# multiplexers.net
KiCad netlist of a schematic drawn in Altium Designer
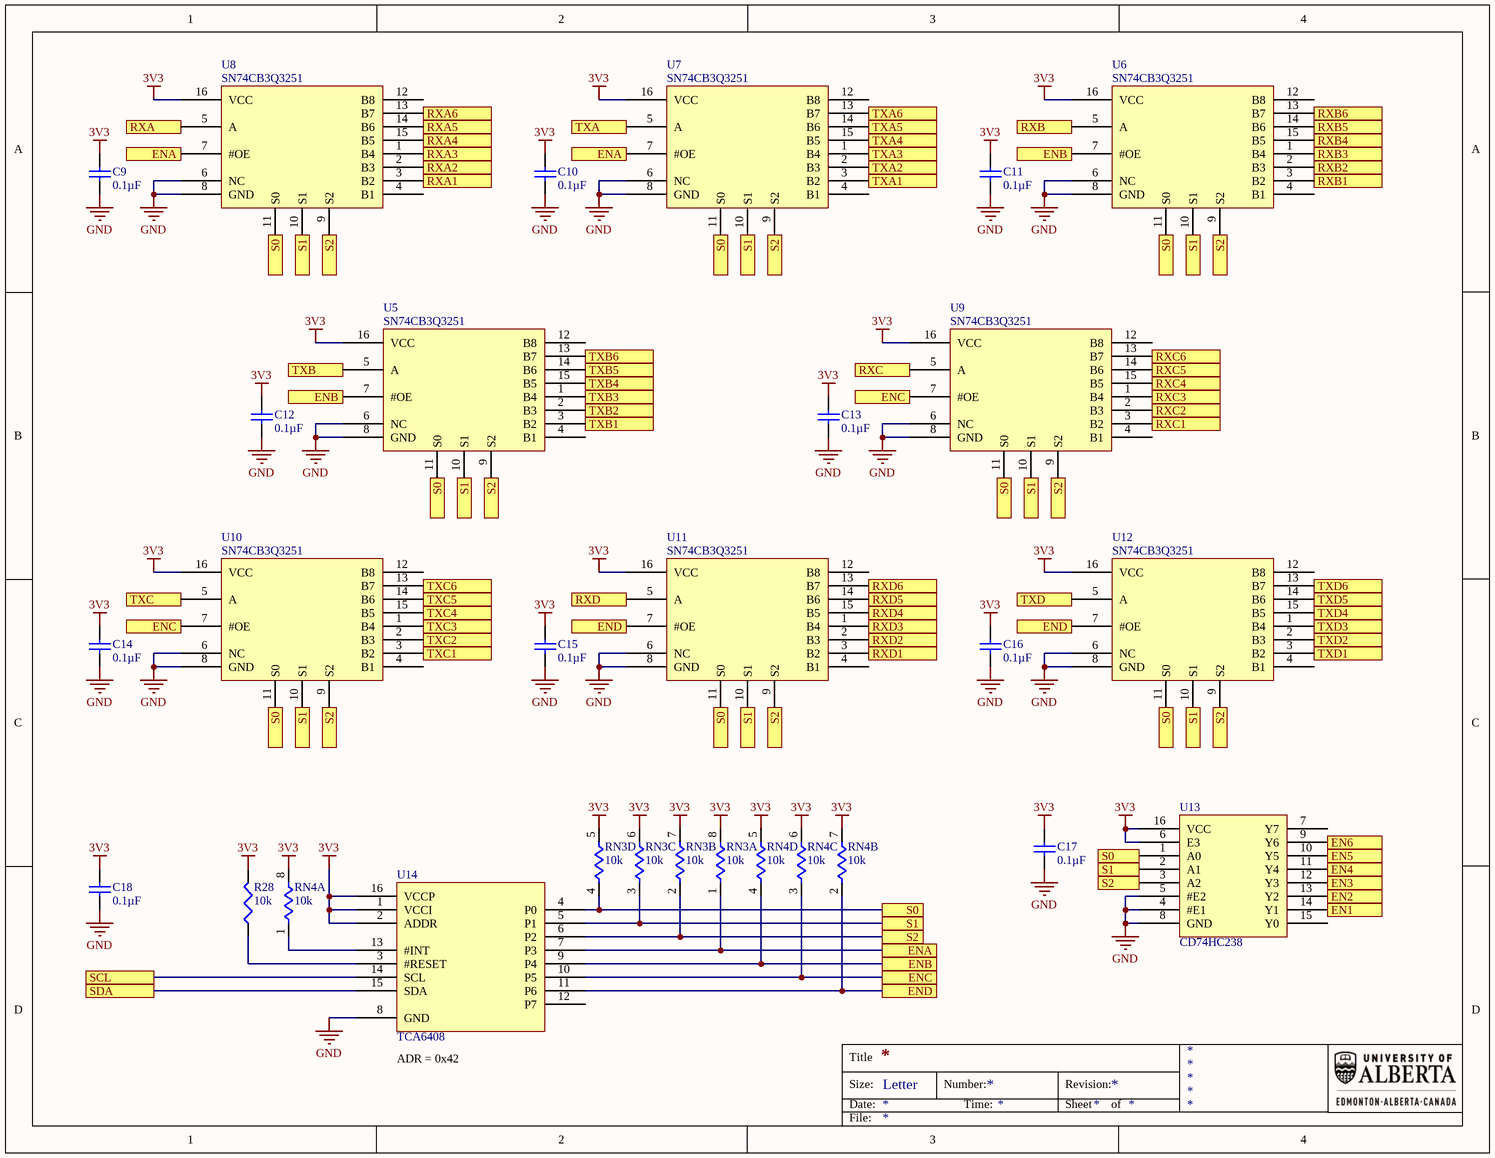
[diagram p0: multiplexers.SchDoc]

(export (version "E")
  (design (tool "Eeschema 10.0.6"))
  (components
    (comp (ref "C9")
      (value "0.1µF")
      (footprint "TDK-CGA3E")
      (description "CAP CER 0.1UF 50V X8R 0603")
      (fields
        (field (name "PART NUMBER") "PC-TDK-02273")
        (field (name "MANUFACTURER PART NUMBER") "CGA3E3X8R1H104M080AB")
        (field (name "PUBLISHER") "AlbertaSat")
      )
      (libsource (lib "Database") (part "Cap"))
    )
    (comp (ref "C10")
      (value "0.1µF")
      (footprint "TDK-CGA3E")
      (description "CAP CER 0.1UF 50V X8R 0603")
      (fields
        (field (name "PART NUMBER") "PC-TDK-02273")
        (field (name "MANUFACTURER PART NUMBER") "CGA3E3X8R1H104M080AB")
        (field (name "PUBLISHER") "AlbertaSat")
      )
      (libsource (lib "Database") (part "Cap"))
    )
    (comp (ref "C11")
      (value "0.1µF")
      (footprint "TDK-CGA3E")
      (description "CAP CER 0.1UF 50V X8R 0603")
      (fields
        (field (name "PART NUMBER") "PC-TDK-02273")
        (field (name "MANUFACTURER PART NUMBER") "CGA3E3X8R1H104M080AB")
        (field (name "PUBLISHER") "AlbertaSat")
      )
      (libsource (lib "Database") (part "Cap"))
    )
    (comp (ref "C12")
      (value "0.1µF")
      (footprint "TDK-CGA3E")
      (description "CAP CER 0.1UF 50V X8R 0603")
      (fields
        (field (name "PART NUMBER") "PC-TDK-02273")
        (field (name "MANUFACTURER PART NUMBER") "CGA3E3X8R1H104M080AB")
        (field (name "PUBLISHER") "AlbertaSat")
      )
      (libsource (lib "Database") (part "Cap"))
    )
    (comp (ref "C13")
      (value "0.1µF")
      (footprint "TDK-CGA3E")
      (description "CAP CER 0.1UF 50V X8R 0603")
      (fields
        (field (name "PART NUMBER") "PC-TDK-02273")
        (field (name "MANUFACTURER PART NUMBER") "CGA3E3X8R1H104M080AB")
        (field (name "PUBLISHER") "AlbertaSat")
      )
      (libsource (lib "Database") (part "Cap"))
    )
    (comp (ref "C14")
      (value "0.1µF")
      (footprint "TDK-CGA3E")
      (description "CAP CER 0.1UF 50V X8R 0603")
      (fields
        (field (name "PART NUMBER") "PC-TDK-02273")
        (field (name "MANUFACTURER PART NUMBER") "CGA3E3X8R1H104M080AB")
        (field (name "PUBLISHER") "AlbertaSat")
      )
      (libsource (lib "Database") (part "Cap"))
    )
    (comp (ref "C15")
      (value "0.1µF")
      (footprint "TDK-CGA3E")
      (description "CAP CER 0.1UF 50V X8R 0603")
      (fields
        (field (name "PART NUMBER") "PC-TDK-02273")
        (field (name "MANUFACTURER PART NUMBER") "CGA3E3X8R1H104M080AB")
        (field (name "PUBLISHER") "AlbertaSat")
      )
      (libsource (lib "Database") (part "Cap"))
    )
    (comp (ref "C16")
      (value "0.1µF")
      (footprint "TDK-CGA3E")
      (description "CAP CER 0.1UF 50V X8R 0603")
      (fields
        (field (name "PART NUMBER") "PC-TDK-02273")
        (field (name "MANUFACTURER PART NUMBER") "CGA3E3X8R1H104M080AB")
        (field (name "PUBLISHER") "AlbertaSat")
      )
      (libsource (lib "Database") (part "Cap"))
    )
    (comp (ref "C17")
      (value "0.1µF")
      (footprint "TDK-CGA3E")
      (description "CAP CER 0.1UF 50V X8R 0603")
      (fields
        (field (name "PART NUMBER") "PC-TDK-02273")
        (field (name "MANUFACTURER PART NUMBER") "CGA3E3X8R1H104M080AB")
        (field (name "PUBLISHER") "AlbertaSat")
      )
      (libsource (lib "Database") (part "Cap"))
    )
    (comp (ref "C18")
      (value "0.1µF")
      (footprint "TDK-CGA3E")
      (description "CAP CER 0.1UF 50V X8R 0603")
      (fields
        (field (name "PART NUMBER") "PC-TDK-02273")
        (field (name "MANUFACTURER PART NUMBER") "CGA3E3X8R1H104M080AB")
        (field (name "PUBLISHER") "AlbertaSat")
      )
      (libsource (lib "Database") (part "Cap"))
    )
    (comp (ref "R28")
      (value "10k")
      (footprint "PANA-ERJ3EK")
      (description "RES SMD 10K OHM 1% 1/10W 0603")
      (fields
        (field (name "PART NUMBER") "17203")
        (field (name "MANUFACTURER PART NUMBER") "ERJ-3EKF1002V")
        (field (name "PUBLISHER") "Altium Limited")
      )
      (libsource (lib "Database") (part "Res3"))
    )
    (comp (ref "RN3")
      (value "10k")
      (footprint "PANA-EXB1206")
      (description "RES ARRAY 4 RES 10K OHM 1206")
      (fields (field (name "PART NUMBER") "19842") (field (name "MANUFACTURER PART NUMBER") "EXB-38V103JV"))
      (libsource (lib "Database") (part "Res4 Pack1"))
    )
    (comp (ref "RN4")
      (value "10k")
      (footprint "PANA-EXB1206")
      (description "RES ARRAY 4 RES 10K OHM 1206")
      (fields (field (name "PART NUMBER") "19842") (field (name "MANUFACTURER PART NUMBER") "EXB-38V103JV"))
      (libsource (lib "Database") (part "Res4 Pack1"))
    )
    (comp (ref "U5")
      (value "SN74CB3Q3251")
      (footprint "TI-PW")
      (description "IC HI-BAND MUX/DEMUX 16-TSSOP")
      (fields (field (name "PART NUMBER") "42") (field (name "MANUFACTURER PART NUMBER") "SN74CB3Q3251PWR"))
      (libsource (lib "Database") (part "SN74CB3Q3251"))
    )
    (comp (ref "U6")
      (value "SN74CB3Q3251")
      (footprint "TI-PW")
      (description "IC HI-BAND MUX/DEMUX 16-TSSOP")
      (fields (field (name "PART NUMBER") "42") (field (name "MANUFACTURER PART NUMBER") "SN74CB3Q3251PWR"))
      (libsource (lib "Database") (part "SN74CB3Q3251"))
    )
    (comp (ref "U7")
      (value "SN74CB3Q3251")
      (footprint "TI-PW")
      (description "IC HI-BAND MUX/DEMUX 16-TSSOP")
      (fields (field (name "PART NUMBER") "42") (field (name "MANUFACTURER PART NUMBER") "SN74CB3Q3251PWR"))
      (libsource (lib "Database") (part "SN74CB3Q3251"))
    )
    (comp (ref "U8")
      (value "SN74CB3Q3251")
      (footprint "TI-PW")
      (description "IC HI-BAND MUX/DEMUX 16-TSSOP")
      (fields (field (name "PART NUMBER") "42") (field (name "MANUFACTURER PART NUMBER") "SN74CB3Q3251PWR"))
      (libsource (lib "Database") (part "SN74CB3Q3251"))
    )
    (comp (ref "U9")
      (value "SN74CB3Q3251")
      (footprint "TI-PW")
      (description "IC HI-BAND MUX/DEMUX 16-TSSOP")
      (fields (field (name "PART NUMBER") "42") (field (name "MANUFACTURER PART NUMBER") "SN74CB3Q3251PWR"))
      (libsource (lib "Database") (part "SN74CB3Q3251"))
    )
    (comp (ref "U10")
      (value "SN74CB3Q3251")
      (footprint "TI-PW")
      (description "IC HI-BAND MUX/DEMUX 16-TSSOP")
      (fields (field (name "PART NUMBER") "42") (field (name "MANUFACTURER PART NUMBER") "SN74CB3Q3251PWR"))
      (libsource (lib "Database") (part "SN74CB3Q3251"))
    )
    (comp (ref "U11")
      (value "SN74CB3Q3251")
      (footprint "TI-PW")
      (description "IC HI-BAND MUX/DEMUX 16-TSSOP")
      (fields (field (name "PART NUMBER") "42") (field (name "MANUFACTURER PART NUMBER") "SN74CB3Q3251PWR"))
      (libsource (lib "Database") (part "SN74CB3Q3251"))
    )
    (comp (ref "U12")
      (value "SN74CB3Q3251")
      (footprint "TI-PW")
      (description "IC HI-BAND MUX/DEMUX 16-TSSOP")
      (fields (field (name "PART NUMBER") "42") (field (name "MANUFACTURER PART NUMBER") "SN74CB3Q3251PWR"))
      (libsource (lib "Database") (part "SN74CB3Q3251"))
    )
    (comp (ref "U13")
      (value "CD74HC238")
      (footprint "TI-PW")
      (description "IC DECODER/DEMUX HS 3-8 16TSSOP")
      (fields (field (name "PART NUMBER") "45") (field (name "MANUFACTURER PART NUMBER") "CD74HC238PW"))
      (libsource (lib "Database") (part "CD74HC238"))
    )
    (comp (ref "U14")
      (value "TCA6408")
      (footprint "TI-PW")
      (description "IC I/O EXPANDER I2C 8B 16TSSOP")
      (fields (field (name "PART NUMBER") "46") (field (name "MANUFACTURER PART NUMBER") "TCA6408AQPWRQ1"))
      (libsource (lib "Database") (part "TCA6408AQ"))
    )
  )
  (nets
    (net (code "1") (name "/EN1") (class "Default")
      (node (ref "U13") (pin "14") (pinfunction "Y1_14") (pintype "passive"))
    )
    (net (code "2") (name "/EN2") (class "Default")
      (node (ref "U13") (pin "13") (pinfunction "Y2_13") (pintype "passive"))
    )
    (net (code "3") (name "/EN3") (class "Default")
      (node (ref "U13") (pin "12") (pinfunction "Y3_12") (pintype "passive"))
    )
    (net (code "4") (name "/EN4") (class "Default")
      (node (ref "U13") (pin "11") (pinfunction "Y4_11") (pintype "passive"))
    )
    (net (code "5") (name "/EN5") (class "Default")
      (node (ref "U13") (pin "10") (pinfunction "Y5_10") (pintype "passive"))
    )
    (net (code "6") (name "/EN6") (class "Default")
      (node (ref "U13") (pin "9") (pinfunction "Y6_9") (pintype "passive"))
    )
    (net (code "7") (name "/ENA") (class "Default")
      (node (ref "RN3") (pin "1") (pinfunction "1_1") (pintype "passive"))
      (node (ref "U14") (pin "7") (pinfunction "P3_7") (pintype "passive"))
      (node (ref "U7") (pin "7") (pinfunction "#OE_7") (pintype "passive"))
      (node (ref "U8") (pin "7") (pinfunction "#OE_7") (pintype "passive"))
    )
    (net (code "8") (name "/ENB") (class "Default")
      (node (ref "RN4") (pin "4") (pinfunction "4_4") (pintype "passive"))
      (node (ref "U14") (pin "9") (pinfunction "P4_9") (pintype "passive"))
      (node (ref "U5") (pin "7") (pinfunction "#OE_7") (pintype "passive"))
      (node (ref "U6") (pin "7") (pinfunction "#OE_7") (pintype "passive"))
    )
    (net (code "9") (name "/ENC") (class "Default")
      (node (ref "RN4") (pin "3") (pinfunction "3_3") (pintype "passive"))
      (node (ref "U10") (pin "7") (pinfunction "#OE_7") (pintype "passive"))
      (node (ref "U14") (pin "10") (pinfunction "P5_10") (pintype "passive"))
      (node (ref "U9") (pin "7") (pinfunction "#OE_7") (pintype "passive"))
    )
    (net (code "10") (name "/END") (class "Default")
      (node (ref "RN4") (pin "2") (pinfunction "2_2") (pintype "passive"))
      (node (ref "U11") (pin "7") (pinfunction "#OE_7") (pintype "passive"))
      (node (ref "U12") (pin "7") (pinfunction "#OE_7") (pintype "passive"))
      (node (ref "U14") (pin "11") (pinfunction "P6_11") (pintype "passive"))
    )
    (net (code "11") (name "/RXA") (class "Default")
      (node (ref "U8") (pin "5") (pinfunction "A_5") (pintype "passive"))
    )
    (net (code "12") (name "/RXA1") (class "Default")
      (node (ref "U8") (pin "3") (pinfunction "B2_3") (pintype "passive"))
    )
    (net (code "13") (name "/RXA2") (class "Default")
      (node (ref "U8") (pin "2") (pinfunction "B3_2") (pintype "passive"))
    )
    (net (code "14") (name "/RXA3") (class "Default")
      (node (ref "U8") (pin "1") (pinfunction "B4_1") (pintype "passive"))
    )
    (net (code "15") (name "/RXA4") (class "Default")
      (node (ref "U8") (pin "15") (pinfunction "B5_15") (pintype "passive"))
    )
    (net (code "16") (name "/RXA5") (class "Default")
      (node (ref "U8") (pin "14") (pinfunction "B6_14") (pintype "passive"))
    )
    (net (code "17") (name "/RXA6") (class "Default")
      (node (ref "U8") (pin "13") (pinfunction "B7_13") (pintype "passive"))
    )
    (net (code "18") (name "/RXB") (class "Default")
      (node (ref "U6") (pin "5") (pinfunction "A_5") (pintype "passive"))
    )
    (net (code "19") (name "/RXB1") (class "Default")
      (node (ref "U6") (pin "3") (pinfunction "B2_3") (pintype "passive"))
    )
    (net (code "20") (name "/RXB2") (class "Default")
      (node (ref "U6") (pin "2") (pinfunction "B3_2") (pintype "passive"))
    )
    (net (code "21") (name "/RXB3") (class "Default")
      (node (ref "U6") (pin "1") (pinfunction "B4_1") (pintype "passive"))
    )
    (net (code "22") (name "/RXB4") (class "Default")
      (node (ref "U6") (pin "15") (pinfunction "B5_15") (pintype "passive"))
    )
    (net (code "23") (name "/RXB5") (class "Default")
      (node (ref "U6") (pin "14") (pinfunction "B6_14") (pintype "passive"))
    )
    (net (code "24") (name "/RXB6") (class "Default")
      (node (ref "U6") (pin "13") (pinfunction "B7_13") (pintype "passive"))
    )
    (net (code "25") (name "/RXC") (class "Default")
      (node (ref "U9") (pin "5") (pinfunction "A_5") (pintype "passive"))
    )
    (net (code "26") (name "/RXC1") (class "Default")
      (node (ref "U9") (pin "3") (pinfunction "B2_3") (pintype "passive"))
    )
    (net (code "27") (name "/RXC2") (class "Default")
      (node (ref "U9") (pin "2") (pinfunction "B3_2") (pintype "passive"))
    )
    (net (code "28") (name "/RXC3") (class "Default")
      (node (ref "U9") (pin "1") (pinfunction "B4_1") (pintype "passive"))
    )
    (net (code "29") (name "/RXC4") (class "Default")
      (node (ref "U9") (pin "15") (pinfunction "B5_15") (pintype "passive"))
    )
    (net (code "30") (name "/RXC5") (class "Default")
      (node (ref "U9") (pin "14") (pinfunction "B6_14") (pintype "passive"))
    )
    (net (code "31") (name "/RXC6") (class "Default")
      (node (ref "U9") (pin "13") (pinfunction "B7_13") (pintype "passive"))
    )
    (net (code "32") (name "/RXD") (class "Default")
      (node (ref "U11") (pin "5") (pinfunction "A_5") (pintype "passive"))
    )
    (net (code "33") (name "/RXD1") (class "Default")
      (node (ref "U11") (pin "3") (pinfunction "B2_3") (pintype "passive"))
    )
    (net (code "34") (name "/RXD2") (class "Default")
      (node (ref "U11") (pin "2") (pinfunction "B3_2") (pintype "passive"))
    )
    (net (code "35") (name "/RXD3") (class "Default")
      (node (ref "U11") (pin "1") (pinfunction "B4_1") (pintype "passive"))
    )
    (net (code "36") (name "/RXD4") (class "Default")
      (node (ref "U11") (pin "15") (pinfunction "B5_15") (pintype "passive"))
    )
    (net (code "37") (name "/RXD5") (class "Default")
      (node (ref "U11") (pin "14") (pinfunction "B6_14") (pintype "passive"))
    )
    (net (code "38") (name "/RXD6") (class "Default")
      (node (ref "U11") (pin "13") (pinfunction "B7_13") (pintype "passive"))
    )
    (net (code "39") (name "/S0") (class "Default")
      (node (ref "RN3") (pin "4") (pinfunction "4_4") (pintype "passive"))
      (node (ref "U10") (pin "11") (pinfunction "S0_11") (pintype "passive"))
      (node (ref "U11") (pin "11") (pinfunction "S0_11") (pintype "passive"))
      (node (ref "U12") (pin "11") (pinfunction "S0_11") (pintype "passive"))
      (node (ref "U13") (pin "1") (pinfunction "A0_1") (pintype "passive"))
      (node (ref "U14") (pin "4") (pinfunction "P0_4") (pintype "passive"))
      (node (ref "U5") (pin "11") (pinfunction "S0_11") (pintype "passive"))
      (node (ref "U6") (pin "11") (pinfunction "S0_11") (pintype "passive"))
      (node (ref "U7") (pin "11") (pinfunction "S0_11") (pintype "passive"))
      (node (ref "U8") (pin "11") (pinfunction "S0_11") (pintype "passive"))
      (node (ref "U9") (pin "11") (pinfunction "S0_11") (pintype "passive"))
    )
    (net (code "40") (name "/S1") (class "Default")
      (node (ref "RN3") (pin "3") (pinfunction "3_3") (pintype "passive"))
      (node (ref "U10") (pin "10") (pinfunction "S1_10") (pintype "passive"))
      (node (ref "U11") (pin "10") (pinfunction "S1_10") (pintype "passive"))
      (node (ref "U12") (pin "10") (pinfunction "S1_10") (pintype "passive"))
      (node (ref "U13") (pin "2") (pinfunction "A1_2") (pintype "passive"))
      (node (ref "U14") (pin "5") (pinfunction "P1_5") (pintype "passive"))
      (node (ref "U5") (pin "10") (pinfunction "S1_10") (pintype "passive"))
      (node (ref "U6") (pin "10") (pinfunction "S1_10") (pintype "passive"))
      (node (ref "U7") (pin "10") (pinfunction "S1_10") (pintype "passive"))
      (node (ref "U8") (pin "10") (pinfunction "S1_10") (pintype "passive"))
      (node (ref "U9") (pin "10") (pinfunction "S1_10") (pintype "passive"))
    )
    (net (code "41") (name "/S2") (class "Default")
      (node (ref "RN3") (pin "2") (pinfunction "2_2") (pintype "passive"))
      (node (ref "U10") (pin "9") (pinfunction "S2_9") (pintype "passive"))
      (node (ref "U11") (pin "9") (pinfunction "S2_9") (pintype "passive"))
      (node (ref "U12") (pin "9") (pinfunction "S2_9") (pintype "passive"))
      (node (ref "U13") (pin "3") (pinfunction "A2_3") (pintype "passive"))
      (node (ref "U14") (pin "6") (pinfunction "P2_6") (pintype "passive"))
      (node (ref "U5") (pin "9") (pinfunction "S2_9") (pintype "passive"))
      (node (ref "U6") (pin "9") (pinfunction "S2_9") (pintype "passive"))
      (node (ref "U7") (pin "9") (pinfunction "S2_9") (pintype "passive"))
      (node (ref "U8") (pin "9") (pinfunction "S2_9") (pintype "passive"))
      (node (ref "U9") (pin "9") (pinfunction "S2_9") (pintype "passive"))
    )
    (net (code "42") (name "/SCL") (class "Default")
      (node (ref "U14") (pin "14") (pinfunction "SCL_14") (pintype "passive"))
    )
    (net (code "43") (name "/SDA") (class "Default")
      (node (ref "U14") (pin "15") (pinfunction "SDA_15") (pintype "passive"))
    )
    (net (code "44") (name "/TXA") (class "Default")
      (node (ref "U7") (pin "5") (pinfunction "A_5") (pintype "passive"))
    )
    (net (code "45") (name "/TXA1") (class "Default")
      (node (ref "U7") (pin "3") (pinfunction "B2_3") (pintype "passive"))
    )
    (net (code "46") (name "/TXA2") (class "Default")
      (node (ref "U7") (pin "2") (pinfunction "B3_2") (pintype "passive"))
    )
    (net (code "47") (name "/TXA3") (class "Default")
      (node (ref "U7") (pin "1") (pinfunction "B4_1") (pintype "passive"))
    )
    (net (code "48") (name "/TXA4") (class "Default")
      (node (ref "U7") (pin "15") (pinfunction "B5_15") (pintype "passive"))
    )
    (net (code "49") (name "/TXA5") (class "Default")
      (node (ref "U7") (pin "14") (pinfunction "B6_14") (pintype "passive"))
    )
    (net (code "50") (name "/TXA6") (class "Default")
      (node (ref "U7") (pin "13") (pinfunction "B7_13") (pintype "passive"))
    )
    (net (code "51") (name "/TXB") (class "Default")
      (node (ref "U5") (pin "5") (pinfunction "A_5") (pintype "passive"))
    )
    (net (code "52") (name "/TXB1") (class "Default")
      (node (ref "U5") (pin "3") (pinfunction "B2_3") (pintype "passive"))
    )
    (net (code "53") (name "/TXB2") (class "Default")
      (node (ref "U5") (pin "2") (pinfunction "B3_2") (pintype "passive"))
    )
    (net (code "54") (name "/TXB3") (class "Default")
      (node (ref "U5") (pin "1") (pinfunction "B4_1") (pintype "passive"))
    )
    (net (code "55") (name "/TXB4") (class "Default")
      (node (ref "U5") (pin "15") (pinfunction "B5_15") (pintype "passive"))
    )
    (net (code "56") (name "/TXB5") (class "Default")
      (node (ref "U5") (pin "14") (pinfunction "B6_14") (pintype "passive"))
    )
    (net (code "57") (name "/TXB6") (class "Default")
      (node (ref "U5") (pin "13") (pinfunction "B7_13") (pintype "passive"))
    )
    (net (code "58") (name "/TXC") (class "Default")
      (node (ref "U10") (pin "5") (pinfunction "A_5") (pintype "passive"))
    )
    (net (code "59") (name "/TXC1") (class "Default")
      (node (ref "U10") (pin "3") (pinfunction "B2_3") (pintype "passive"))
    )
    (net (code "60") (name "/TXC2") (class "Default")
      (node (ref "U10") (pin "2") (pinfunction "B3_2") (pintype "passive"))
    )
    (net (code "61") (name "/TXC3") (class "Default")
      (node (ref "U10") (pin "1") (pinfunction "B4_1") (pintype "passive"))
    )
    (net (code "62") (name "/TXC4") (class "Default")
      (node (ref "U10") (pin "15") (pinfunction "B5_15") (pintype "passive"))
    )
    (net (code "63") (name "/TXC5") (class "Default")
      (node (ref "U10") (pin "14") (pinfunction "B6_14") (pintype "passive"))
    )
    (net (code "64") (name "/TXC6") (class "Default")
      (node (ref "U10") (pin "13") (pinfunction "B7_13") (pintype "passive"))
    )
    (net (code "65") (name "/TXD") (class "Default")
      (node (ref "U12") (pin "5") (pinfunction "A_5") (pintype "passive"))
    )
    (net (code "66") (name "/TXD1") (class "Default")
      (node (ref "U12") (pin "3") (pinfunction "B2_3") (pintype "passive"))
    )
    (net (code "67") (name "/TXD2") (class "Default")
      (node (ref "U12") (pin "2") (pinfunction "B3_2") (pintype "passive"))
    )
    (net (code "68") (name "/TXD3") (class "Default")
      (node (ref "U12") (pin "1") (pinfunction "B4_1") (pintype "passive"))
    )
    (net (code "69") (name "/TXD4") (class "Default")
      (node (ref "U12") (pin "15") (pinfunction "B5_15") (pintype "passive"))
    )
    (net (code "70") (name "/TXD5") (class "Default")
      (node (ref "U12") (pin "14") (pinfunction "B6_14") (pintype "passive"))
    )
    (net (code "71") (name "/TXD6") (class "Default")
      (node (ref "U12") (pin "13") (pinfunction "B7_13") (pintype "passive"))
    )
    (net (code "72") (name "3V3") (class "Default")
      (node (ref "C10") (pin "2") (pinfunction "2_2") (pintype "passive"))
      (node (ref "C11") (pin "2") (pinfunction "2_2") (pintype "passive"))
      (node (ref "C12") (pin "2") (pinfunction "2_2") (pintype "passive"))
      (node (ref "C13") (pin "2") (pinfunction "2_2") (pintype "passive"))
      (node (ref "C14") (pin "2") (pinfunction "2_2") (pintype "passive"))
      (node (ref "C15") (pin "2") (pinfunction "2_2") (pintype "passive"))
      (node (ref "C16") (pin "2") (pinfunction "2_2") (pintype "passive"))
      (node (ref "C17") (pin "2") (pinfunction "2_2") (pintype "passive"))
      (node (ref "C18") (pin "2") (pinfunction "2_2") (pintype "passive"))
      (node (ref "C9") (pin "2") (pinfunction "2_2") (pintype "passive"))
      (node (ref "R28") (pin "2") (pinfunction "2_2") (pintype "passive"))
      (node (ref "RN3") (pin "5") (pinfunction "5_5") (pintype "passive"))
      (node (ref "RN3") (pin "6") (pinfunction "6_6") (pintype "passive"))
      (node (ref "RN3") (pin "7") (pinfunction "7_7") (pintype "passive"))
      (node (ref "RN3") (pin "8") (pinfunction "8_8") (pintype "passive"))
      (node (ref "RN4") (pin "5") (pinfunction "5_5") (pintype "passive"))
      (node (ref "RN4") (pin "6") (pinfunction "6_6") (pintype "passive"))
      (node (ref "RN4") (pin "7") (pinfunction "7_7") (pintype "passive"))
      (node (ref "RN4") (pin "8") (pinfunction "8_8") (pintype "passive"))
      (node (ref "U10") (pin "16") (pinfunction "VCC_16") (pintype "passive"))
      (node (ref "U11") (pin "16") (pinfunction "VCC_16") (pintype "passive"))
      (node (ref "U12") (pin "16") (pinfunction "VCC_16") (pintype "passive"))
      (node (ref "U13") (pin "16") (pinfunction "VCC_16") (pintype "passive"))
      (node (ref "U13") (pin "6") (pinfunction "E3_6") (pintype "passive"))
      (node (ref "U14") (pin "1") (pinfunction "VCCI_1") (pintype "passive"))
      (node (ref "U14") (pin "16") (pinfunction "VCCP_16") (pintype "passive"))
      (node (ref "U14") (pin "2") (pinfunction "ADDR_2") (pintype "passive"))
      (node (ref "U5") (pin "16") (pinfunction "VCC_16") (pintype "passive"))
      (node (ref "U6") (pin "16") (pinfunction "VCC_16") (pintype "passive"))
      (node (ref "U7") (pin "16") (pinfunction "VCC_16") (pintype "passive"))
      (node (ref "U8") (pin "16") (pinfunction "VCC_16") (pintype "passive"))
      (node (ref "U9") (pin "16") (pinfunction "VCC_16") (pintype "passive"))
    )
    (net (code "73") (name "GND") (class "Default")
      (node (ref "C10") (pin "1") (pinfunction "1_1") (pintype "passive"))
      (node (ref "C11") (pin "1") (pinfunction "1_1") (pintype "passive"))
      (node (ref "C12") (pin "1") (pinfunction "1_1") (pintype "passive"))
      (node (ref "C13") (pin "1") (pinfunction "1_1") (pintype "passive"))
      (node (ref "C14") (pin "1") (pinfunction "1_1") (pintype "passive"))
      (node (ref "C15") (pin "1") (pinfunction "1_1") (pintype "passive"))
      (node (ref "C16") (pin "1") (pinfunction "1_1") (pintype "passive"))
      (node (ref "C17") (pin "1") (pinfunction "1_1") (pintype "passive"))
      (node (ref "C18") (pin "1") (pinfunction "1_1") (pintype "passive"))
      (node (ref "C9") (pin "1") (pinfunction "1_1") (pintype "passive"))
      (node (ref "U10") (pin "6") (pinfunction "NC_6") (pintype "passive"))
      (node (ref "U10") (pin "8") (pinfunction "GND_8") (pintype "passive"))
      (node (ref "U11") (pin "6") (pinfunction "NC_6") (pintype "passive"))
      (node (ref "U11") (pin "8") (pinfunction "GND_8") (pintype "passive"))
      (node (ref "U12") (pin "6") (pinfunction "NC_6") (pintype "passive"))
      (node (ref "U12") (pin "8") (pinfunction "GND_8") (pintype "passive"))
      (node (ref "U13") (pin "4") (pinfunction "#E1_4") (pintype "passive"))
      (node (ref "U13") (pin "5") (pinfunction "#E2_5") (pintype "passive"))
      (node (ref "U13") (pin "8") (pinfunction "GND_8") (pintype "passive"))
      (node (ref "U14") (pin "8") (pinfunction "GND_8") (pintype "passive"))
      (node (ref "U5") (pin "6") (pinfunction "NC_6") (pintype "passive"))
      (node (ref "U5") (pin "8") (pinfunction "GND_8") (pintype "passive"))
      (node (ref "U6") (pin "6") (pinfunction "NC_6") (pintype "passive"))
      (node (ref "U6") (pin "8") (pinfunction "GND_8") (pintype "passive"))
      (node (ref "U7") (pin "6") (pinfunction "NC_6") (pintype "passive"))
      (node (ref "U7") (pin "8") (pinfunction "GND_8") (pintype "passive"))
      (node (ref "U8") (pin "6") (pinfunction "NC_6") (pintype "passive"))
      (node (ref "U8") (pin "8") (pinfunction "GND_8") (pintype "passive"))
      (node (ref "U9") (pin "6") (pinfunction "NC_6") (pintype "passive"))
      (node (ref "U9") (pin "8") (pinfunction "GND_8") (pintype "passive"))
    )
    (net (code "74") (name "Net-(U14-#INT)") (class "Default")
      (node (ref "RN4") (pin "1") (pinfunction "1_1") (pintype "passive"))
      (node (ref "U14") (pin "13") (pinfunction "#INT_13") (pintype "passive"))
    )
    (net (code "75") (name "Net-(U14-#RESET)") (class "Default")
      (node (ref "R28") (pin "1") (pinfunction "1_1") (pintype "passive"))
      (node (ref "U14") (pin "3") (pinfunction "#RESET_3") (pintype "passive"))
    )
    (net (code "76") (name "unconnected-(U5-B1-Pad4)") (class "Default")
      (node (ref "U5") (pin "4") (pinfunction "B1_4") (pintype "passive"))
    )
    (net (code "77") (name "unconnected-(U5-B8-Pad12)") (class "Default")
      (node (ref "U5") (pin "12") (pinfunction "B8_12") (pintype "passive"))
    )
    (net (code "78") (name "unconnected-(U6-B1-Pad4)") (class "Default")
      (node (ref "U6") (pin "4") (pinfunction "B1_4") (pintype "passive"))
    )
    (net (code "79") (name "unconnected-(U6-B8-Pad12)") (class "Default")
      (node (ref "U6") (pin "12") (pinfunction "B8_12") (pintype "passive"))
    )
    (net (code "80") (name "unconnected-(U7-B1-Pad4)") (class "Default")
      (node (ref "U7") (pin "4") (pinfunction "B1_4") (pintype "passive"))
    )
    (net (code "81") (name "unconnected-(U7-B8-Pad12)") (class "Default")
      (node (ref "U7") (pin "12") (pinfunction "B8_12") (pintype "passive"))
    )
    (net (code "82") (name "unconnected-(U8-B1-Pad4)") (class "Default")
      (node (ref "U8") (pin "4") (pinfunction "B1_4") (pintype "passive"))
    )
    (net (code "83") (name "unconnected-(U8-B8-Pad12)") (class "Default")
      (node (ref "U8") (pin "12") (pinfunction "B8_12") (pintype "passive"))
    )
    (net (code "84") (name "unconnected-(U9-B1-Pad4)") (class "Default")
      (node (ref "U9") (pin "4") (pinfunction "B1_4") (pintype "passive"))
    )
    (net (code "85") (name "unconnected-(U9-B8-Pad12)") (class "Default")
      (node (ref "U9") (pin "12") (pinfunction "B8_12") (pintype "passive"))
    )
    (net (code "86") (name "unconnected-(U10-B1-Pad4)") (class "Default")
      (node (ref "U10") (pin "4") (pinfunction "B1_4") (pintype "passive"))
    )
    (net (code "87") (name "unconnected-(U10-B8-Pad12)") (class "Default")
      (node (ref "U10") (pin "12") (pinfunction "B8_12") (pintype "passive"))
    )
    (net (code "88") (name "unconnected-(U11-B1-Pad4)") (class "Default")
      (node (ref "U11") (pin "4") (pinfunction "B1_4") (pintype "passive"))
    )
    (net (code "89") (name "unconnected-(U11-B8-Pad12)") (class "Default")
      (node (ref "U11") (pin "12") (pinfunction "B8_12") (pintype "passive"))
    )
    (net (code "90") (name "unconnected-(U12-B1-Pad4)") (class "Default")
      (node (ref "U12") (pin "4") (pinfunction "B1_4") (pintype "passive"))
    )
    (net (code "91") (name "unconnected-(U12-B8-Pad12)") (class "Default")
      (node (ref "U12") (pin "12") (pinfunction "B8_12") (pintype "passive"))
    )
    (net (code "92") (name "unconnected-(U13-Y0-Pad15)") (class "Default")
      (node (ref "U13") (pin "15") (pinfunction "Y0_15") (pintype "passive"))
    )
    (net (code "93") (name "unconnected-(U13-Y7-Pad7)") (class "Default")
      (node (ref "U13") (pin "7") (pinfunction "Y7_7") (pintype "passive"))
    )
    (net (code "94") (name "unconnected-(U14-P7-Pad12)") (class "Default")
      (node (ref "U14") (pin "12") (pinfunction "P7_12") (pintype "passive"))
    )
  )
)
